# sw63_mk3_2.net
KiCad netlist of a schematic drawn in EAGLE
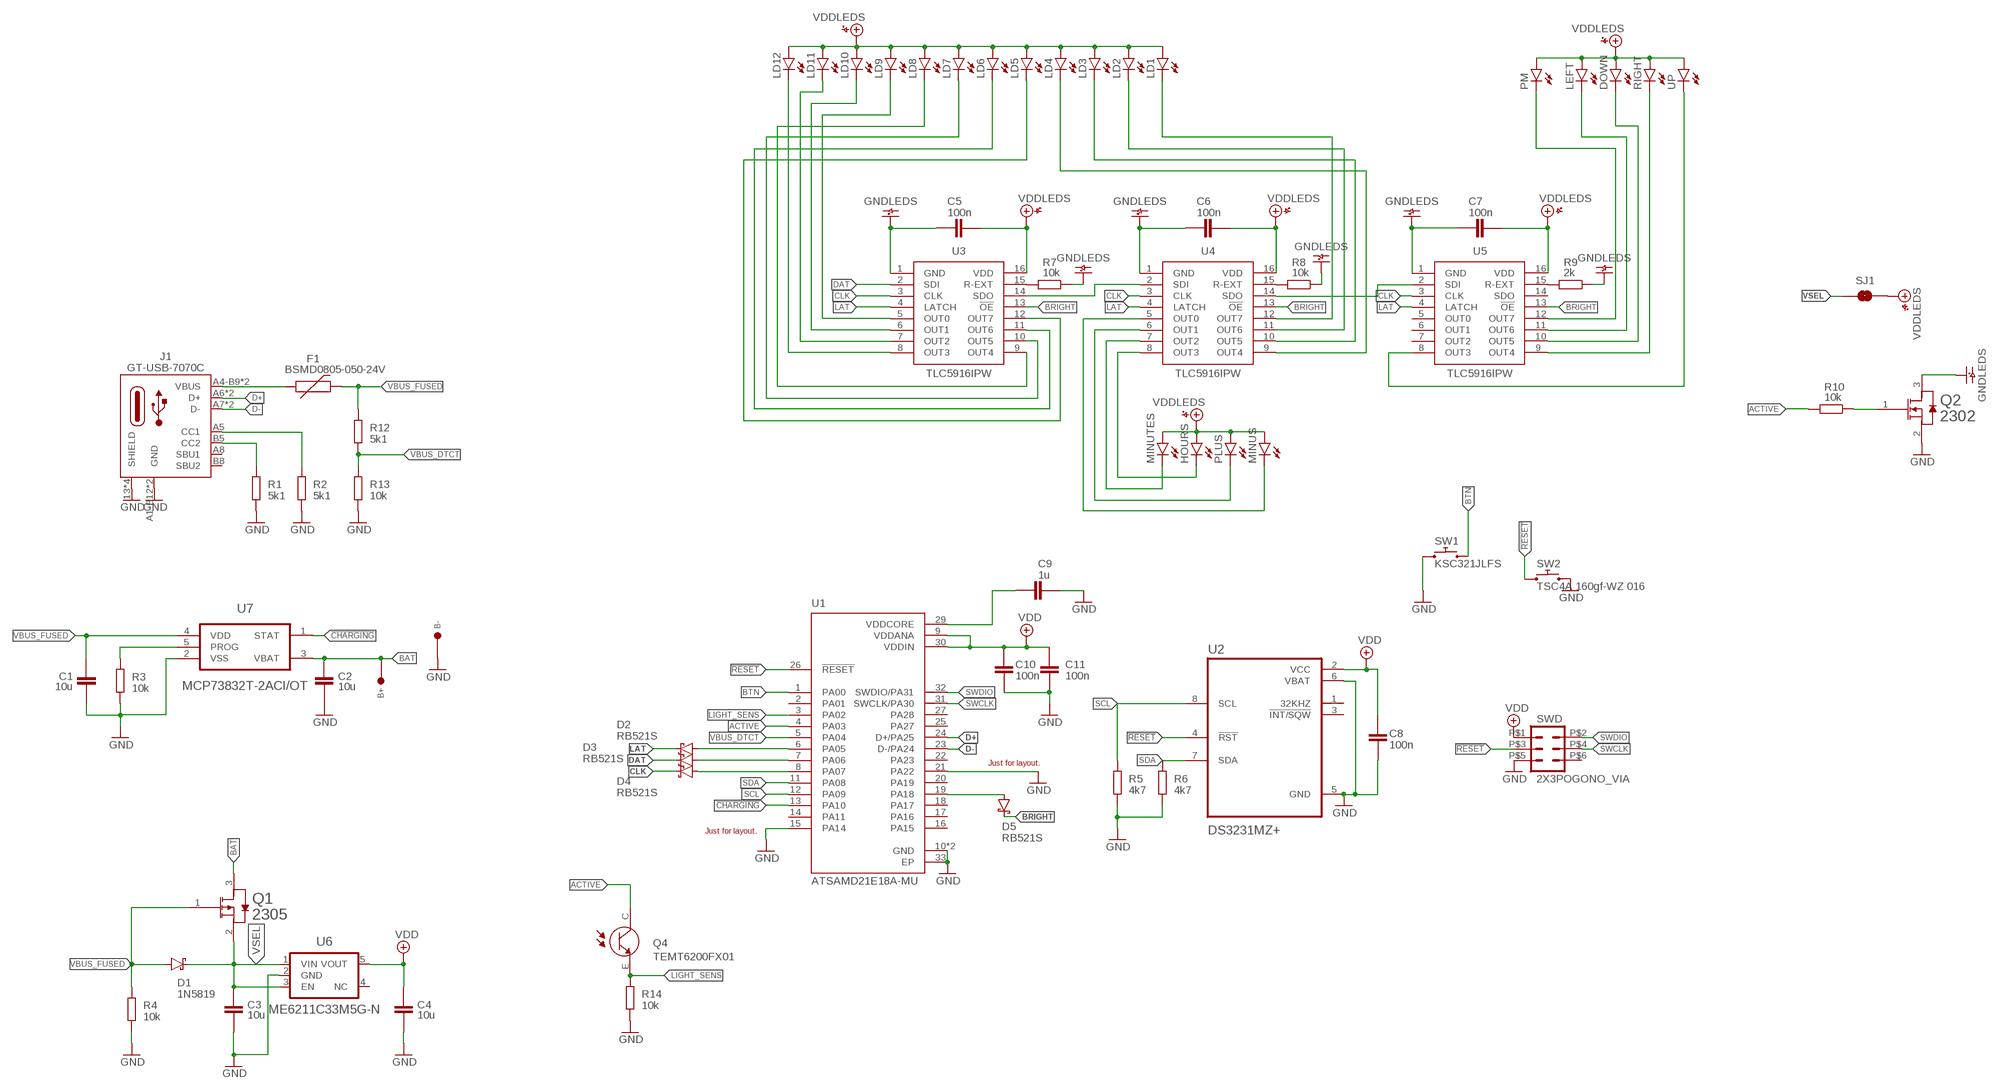
[diagram p0: schematic, sheet 1]

(export (version "E")
  (design (tool "Eeschema 10.0.6"))
  (components
    (comp (ref "B+")
      (value "TEST_PIN_LARGE")
      (footprint "eagle-import:TEST_PIN_2.0")
      (libsource (lib "eagle-import") (part "TEST_PIN_LARGE"))
    )
    (comp (ref "B-")
      (value "TEST_PIN_LARGE")
      (footprint "eagle-import:TEST_PIN_2.0")
      (libsource (lib "eagle-import") (part "TEST_PIN_LARGE"))
    )
    (comp (ref "C1")
      (value "10u")
      (footprint "eagle-import:CAPACITOR0805")
      (libsource (lib "eagle-import") (part "CAPACITOR0805"))
    )
    (comp (ref "C2")
      (value "10u")
      (footprint "eagle-import:CAPACITOR0805")
      (libsource (lib "eagle-import") (part "CAPACITOR0805"))
    )
    (comp (ref "C3")
      (value "10u")
      (footprint "eagle-import:CAPACITOR0805")
      (libsource (lib "eagle-import") (part "CAPACITOR0805"))
    )
    (comp (ref "C4")
      (value "10u")
      (footprint "eagle-import:CAPACITOR0805")
      (libsource (lib "eagle-import") (part "CAPACITOR0805"))
    )
    (comp (ref "C5")
      (value "100n")
      (footprint "eagle-import:CAPACITOR0603")
      (libsource (lib "eagle-import") (part "CAPACITOR0603"))
    )
    (comp (ref "C6")
      (value "100n")
      (footprint "eagle-import:CAPACITOR0603")
      (libsource (lib "eagle-import") (part "CAPACITOR0603"))
    )
    (comp (ref "C7")
      (value "100n")
      (footprint "eagle-import:CAPACITOR0603")
      (libsource (lib "eagle-import") (part "CAPACITOR0603"))
    )
    (comp (ref "C8")
      (value "100n")
      (footprint "eagle-import:CAPACITOR0603")
      (libsource (lib "eagle-import") (part "CAPACITOR0603"))
    )
    (comp (ref "C9")
      (value "1u")
      (footprint "eagle-import:CAPACITOR0603")
      (libsource (lib "eagle-import") (part "CAPACITOR0603"))
    )
    (comp (ref "C10")
      (value "100n")
      (footprint "eagle-import:CAPACITOR0603")
      (libsource (lib "eagle-import") (part "CAPACITOR0603"))
    )
    (comp (ref "C11")
      (value "100n")
      (footprint "eagle-import:CAPACITOR0603")
      (libsource (lib "eagle-import") (part "CAPACITOR0603"))
    )
    (comp (ref "D1")
      (value "1N5819")
      (footprint "eagle-import:SOD123")
      (libsource (lib "eagle-import") (part "SCHOTTKY_DIODE"))
    )
    (comp (ref "D2")
      (value "RB521S")
      (footprint "eagle-import:SOD523")
      (libsource (lib "eagle-import") (part "SCHOTTKY_DIODE_SOD523"))
    )
    (comp (ref "D3")
      (value "RB521S")
      (footprint "eagle-import:SOD523")
      (libsource (lib "eagle-import") (part "SCHOTTKY_DIODE_SOD523"))
    )
    (comp (ref "D4")
      (value "RB521S")
      (footprint "eagle-import:SOD523")
      (libsource (lib "eagle-import") (part "SCHOTTKY_DIODE_SOD523"))
    )
    (comp (ref "D5")
      (value "RB521S")
      (footprint "eagle-import:SOD523")
      (libsource (lib "eagle-import") (part "SCHOTTKY_DIODE_SOD523"))
    )
    (comp (ref "DOWN")
      (value "LED_RECT-3.2X2")
      (footprint "eagle-import:LED_RECT_3.2X2")
      (libsource (lib "eagle-import") (part "LED_RECT-3.2X2"))
    )
    (comp (ref "F1")
      (value "BSMD0805-050-24V")
      (footprint "eagle-import:PTC0805")
      (libsource (lib "eagle-import") (part "PTC"))
    )
    (comp (ref "HOURS")
      (value "LED_THT-5MM_B")
      (footprint "eagle-import:LED_5MM_BLUE")
      (libsource (lib "eagle-import") (part "LED_THT-5MM_B"))
    )
    (comp (ref "J1")
      (value "GT-USB-7070C")
      (footprint "eagle-import:USB-C_FULL_SMT_WS")
      (libsource (lib "eagle-import") (part "USB-C_2.0_SMT_WS"))
    )
    (comp (ref "LD1")
      (value "LED_SMT_1206")
      (footprint "eagle-import:LED_1206")
      (libsource (lib "eagle-import") (part "LED_SMT_1206"))
    )
    (comp (ref "LD2")
      (value "LED_SMT_1206")
      (footprint "eagle-import:LED_1206")
      (libsource (lib "eagle-import") (part "LED_SMT_1206"))
    )
    (comp (ref "LD3")
      (value "LED_SMT_1206")
      (footprint "eagle-import:LED_1206")
      (libsource (lib "eagle-import") (part "LED_SMT_1206"))
    )
    (comp (ref "LD4")
      (value "LED_SMT_1206")
      (footprint "eagle-import:LED_1206")
      (libsource (lib "eagle-import") (part "LED_SMT_1206"))
    )
    (comp (ref "LD5")
      (value "LED_SMT_1206")
      (footprint "eagle-import:LED_1206")
      (libsource (lib "eagle-import") (part "LED_SMT_1206"))
    )
    (comp (ref "LD6")
      (value "LED_SMT_1206")
      (footprint "eagle-import:LED_1206")
      (libsource (lib "eagle-import") (part "LED_SMT_1206"))
    )
    (comp (ref "LD7")
      (value "LED_SMT_1206")
      (footprint "eagle-import:LED_1206")
      (libsource (lib "eagle-import") (part "LED_SMT_1206"))
    )
    (comp (ref "LD8")
      (value "LED_SMT_1206")
      (footprint "eagle-import:LED_1206")
      (libsource (lib "eagle-import") (part "LED_SMT_1206"))
    )
    (comp (ref "LD9")
      (value "LED_SMT_1206")
      (footprint "eagle-import:LED_1206")
      (libsource (lib "eagle-import") (part "LED_SMT_1206"))
    )
    (comp (ref "LD10")
      (value "LED_SMT_1206")
      (footprint "eagle-import:LED_1206")
      (libsource (lib "eagle-import") (part "LED_SMT_1206"))
    )
    (comp (ref "LD11")
      (value "LED_SMT_1206")
      (footprint "eagle-import:LED_1206")
      (libsource (lib "eagle-import") (part "LED_SMT_1206"))
    )
    (comp (ref "LD12")
      (value "LED_SMT_1206")
      (footprint "eagle-import:LED_1206")
      (libsource (lib "eagle-import") (part "LED_SMT_1206"))
    )
    (comp (ref "LEFT")
      (value "LED_RECT-3.2X2")
      (footprint "eagle-import:LED_RECT_3.2X2")
      (libsource (lib "eagle-import") (part "LED_RECT-3.2X2"))
    )
    (comp (ref "MINUS")
      (value "LED_THT-5MM_R")
      (footprint "eagle-import:LED_5MM_RED")
      (libsource (lib "eagle-import") (part "LED_THT-5MM_R"))
    )
    (comp (ref "MINUTES")
      (value "LED_THT-5MM_Y")
      (footprint "eagle-import:LED_5MM_YELLOW")
      (libsource (lib "eagle-import") (part "LED_THT-5MM_Y"))
    )
    (comp (ref "PLUS")
      (value "LED_THT-5MM_G")
      (footprint "eagle-import:LED_5MM_GREEN")
      (libsource (lib "eagle-import") (part "LED_THT-5MM_G"))
    )
    (comp (ref "PM")
      (value "LED_THT-3MM_ALT")
      (footprint "eagle-import:LED_3MM_ALT")
      (libsource (lib "eagle-import") (part "LED_THT-3MM_ALT"))
    )
    (comp (ref "Q1")
      (value "2305")
      (footprint "eagle-import:SOT23")
      (libsource (lib "eagle-import") (part "LGE2305"))
    )
    (comp (ref "Q2")
      (value "2302")
      (footprint "eagle-import:SOT23")
      (libsource (lib "eagle-import") (part "N-MOSFET"))
    )
    (comp (ref "Q4")
      (value "TEMT6200FX01")
      (footprint "eagle-import:TEMT6200FX01")
      (fields (field (name "MF") "Vishay Semiconductor"))
      (libsource (lib "eagle-import") (part "TEMT6200FX01"))
    )
    (comp (ref "R1")
      (value "5k1")
      (footprint "eagle-import:RESISTOR0603")
      (libsource (lib "eagle-import") (part "RESISTOR0603"))
    )
    (comp (ref "R2")
      (value "5k1")
      (footprint "eagle-import:RESISTOR0603")
      (libsource (lib "eagle-import") (part "RESISTOR0603"))
    )
    (comp (ref "R3")
      (value "10k")
      (footprint "eagle-import:RESISTOR0603")
      (libsource (lib "eagle-import") (part "RESISTOR0603"))
    )
    (comp (ref "R4")
      (value "10k")
      (footprint "eagle-import:RESISTOR0603")
      (libsource (lib "eagle-import") (part "RESISTOR0603"))
    )
    (comp (ref "R5")
      (value "4k7")
      (footprint "eagle-import:RESISTOR0603")
      (libsource (lib "eagle-import") (part "RESISTOR0603"))
    )
    (comp (ref "R6")
      (value "4k7")
      (footprint "eagle-import:RESISTOR0603")
      (libsource (lib "eagle-import") (part "RESISTOR0603"))
    )
    (comp (ref "R7")
      (value "10k")
      (footprint "eagle-import:RESISTOR0603")
      (libsource (lib "eagle-import") (part "RESISTOR0603"))
    )
    (comp (ref "R8")
      (value "10k")
      (footprint "eagle-import:RESISTOR0603")
      (libsource (lib "eagle-import") (part "RESISTOR0603"))
    )
    (comp (ref "R9")
      (value "2k")
      (footprint "eagle-import:RESISTOR0603")
      (libsource (lib "eagle-import") (part "RESISTOR0603"))
    )
    (comp (ref "R10")
      (value "10k")
      (footprint "eagle-import:RESISTOR0603")
      (libsource (lib "eagle-import") (part "RESISTOR0603"))
    )
    (comp (ref "R12")
      (value "5k1")
      (footprint "eagle-import:RESISTOR0603")
      (libsource (lib "eagle-import") (part "RESISTOR0603"))
    )
    (comp (ref "R13")
      (value "10k")
      (footprint "eagle-import:RESISTOR0603")
      (libsource (lib "eagle-import") (part "RESISTOR0603"))
    )
    (comp (ref "R14")
      (value "10k")
      (footprint "eagle-import:RESISTOR0603")
      (libsource (lib "eagle-import") (part "RESISTOR0603"))
    )
    (comp (ref "RIGHT")
      (value "LED_RECT-3.2X2")
      (footprint "eagle-import:LED_RECT_3.2X2")
      (libsource (lib "eagle-import") (part "LED_RECT-3.2X2"))
    )
    (comp (ref "SJ1")
      (value "SMALL_NC")
      (footprint "eagle-import:SMALL_NC_NOSILK")
      (libsource (lib "eagle-import") (part "SMALL_NC"))
    )
    (comp (ref "SW1")
      (value "KSC321JLFS")
      (footprint "eagle-import:KSC3XXJ")
      (libsource (lib "eagle-import") (part "KSC3XXJ"))
    )
    (comp (ref "SW2")
      (value "TSC4A 160gf-WZ 016")
      (footprint "eagle-import:EVQ-P7J01P")
      (libsource (lib "eagle-import") (part "EVQ-P7J01P"))
    )
    (comp (ref "SWD")
      (value "2X3POGONO_VIA")
      (footprint "eagle-import:2X3_POGO_NO_VIA")
      (libsource (lib "eagle-import") (part "2X3POGONO_VIA"))
    )
    (comp (ref "U1")
      (value "ATSAMD21E18A-MU")
      (footprint "eagle-import:QFN50P500X500X100-33N")
      (fields (field (name "DIGIKEY_PART_NUMBER") "ATSAMD21E18A-MU-ND") (field (name "MF") "Microchip"))
      (libsource (lib "eagle-import") (part "ATSAMD21E18A-MU"))
    )
    (comp (ref "U2")
      (value "DS3231MZ+")
      (footprint "eagle-import:SO8")
      (fields
        (field (name "DIGI-KEY_PART_NUMBER") "DS3231MZ+-ND")
        (field (name "MF") "Maxim Integrated Products")
      )
      (libsource (lib "eagle-import") (part "DS3231MZ+"))
    )
    (comp (ref "U3")
      (value "TLC5916IPW")
      (footprint "eagle-import:TSSOP16")
      (libsource (lib "eagle-import") (part "TLC5916IPW"))
    )
    (comp (ref "U4")
      (value "TLC5916IPW")
      (footprint "eagle-import:TSSOP16")
      (libsource (lib "eagle-import") (part "TLC5916IPW"))
    )
    (comp (ref "U5")
      (value "TLC5916IPW")
      (footprint "eagle-import:TSSOP16")
      (libsource (lib "eagle-import") (part "TLC5916IPW"))
    )
    (comp (ref "U6")
      (value "ME6211C33M5G-N")
      (footprint "eagle-import:SOT23-5")
      (libsource (lib "eagle-import") (part "MIC5504YM5-TR"))
    )
    (comp (ref "U7")
      (value "MCP73832T-2ACI/OT")
      (footprint "eagle-import:SOT23-5")
      (fields (field (name "MPN") "MCP73831T-2ACI/OT"))
      (libsource (lib "eagle-import") (part "MCP73831T-2ACI"))
    )
    (comp (ref "UP")
      (value "LED_RECT-3.2X2")
      (footprint "eagle-import:LED_RECT_3.2X2")
      (libsource (lib "eagle-import") (part "LED_RECT-3.2X2"))
    )
  )
  (nets
    (net (code "1") (name "/~{CHARGING}") (class "Default")
      (node (ref "U1") (pin "13") (pinfunction "PA10_13") (pintype "bidirectional"))
      (node (ref "U7") (pin "1") (pinfunction "STAT_1") (pintype "output"))
    )
    (net (code "2") (name "/~{RESET}") (class "Default")
      (node (ref "SW2") (pin "1_1") (pinfunction "1_1_1") (pintype "passive"))
      (node (ref "SW2") (pin "1_2") (pinfunction "1_1_2") (pintype "passive"))
      (node (ref "SWD") (pin "P$3") (pinfunction "3_P$3") (pintype "passive"))
      (node (ref "U1") (pin "26") (pinfunction "~{RESET}_26") (pintype "input"))
      (node (ref "U2") (pin "4") (pinfunction "~{RST}_4") (pintype "bidirectional"))
    )
    (net (code "3") (name "ACTIVE") (class "Default")
      (node (ref "Q4") (pin "C") (pinfunction "C_C") (pintype "passive"))
      (node (ref "R10") (pin "2") (pinfunction "2_2") (pintype "passive"))
      (node (ref "U1") (pin "4") (pinfunction "PA03_4") (pintype "bidirectional"))
    )
    (net (code "4") (name "BAT") (class "Default")
      (node (ref "B+") (pin "P$1") (pinfunction "P$1_P$1") (pintype "bidirectional"))
      (node (ref "C2") (pin "1") (pinfunction "1_1") (pintype "passive"))
      (node (ref "Q1") (pin "3") (pinfunction "DRAIN_3") (pintype "passive"))
      (node (ref "U7") (pin "3") (pinfunction "VBAT_3") (pintype "output"))
    )
    (net (code "5") (name "BRIGHT") (class "Default")
      (node (ref "D5") (pin "C") (pinfunction "C_C") (pintype "passive"))
      (node (ref "U3") (pin "13") (pinfunction "~{OE}_13") (pintype "input"))
      (node (ref "U4") (pin "13") (pinfunction "~{OE}_13") (pintype "input"))
      (node (ref "U5") (pin "13") (pinfunction "~{OE}_13") (pintype "input"))
    )
    (net (code "6") (name "BTN") (class "Default")
      (node (ref "SW1") (pin "2") (pinfunction "2_2") (pintype "passive"))
      (node (ref "SW1") (pin "4") (pinfunction "2_4") (pintype "passive"))
      (node (ref "U1") (pin "1") (pinfunction "PA00_1") (pintype "bidirectional"))
    )
    (net (code "7") (name "CLK") (class "Default")
      (node (ref "D4") (pin "C") (pinfunction "C_C") (pintype "passive"))
      (node (ref "U3") (pin "3") (pinfunction "CLK_3") (pintype "input"))
      (node (ref "U4") (pin "3") (pinfunction "CLK_3") (pintype "input"))
      (node (ref "U5") (pin "3") (pinfunction "CLK_3") (pintype "input"))
    )
    (net (code "8") (name "D+") (class "Default")
      (node (ref "J1") (pin "A6") (pinfunction "D+_A6") (pintype "bidirectional"))
      (node (ref "J1") (pin "B6") (pinfunction "D+_B6") (pintype "bidirectional"))
      (node (ref "U1") (pin "24") (pinfunction "D+/PA25_24") (pintype "bidirectional"))
    )
    (net (code "9") (name "D-") (class "Default")
      (node (ref "J1") (pin "A7") (pinfunction "D-_A7") (pintype "bidirectional"))
      (node (ref "J1") (pin "B7") (pinfunction "D-_B7") (pintype "bidirectional"))
      (node (ref "U1") (pin "23") (pinfunction "D-/PA24_23") (pintype "bidirectional"))
    )
    (net (code "10") (name "DAT") (class "Default")
      (node (ref "D3") (pin "C") (pinfunction "C_C") (pintype "passive"))
      (node (ref "U3") (pin "2") (pinfunction "SDI_2") (pintype "input"))
    )
    (net (code "11") (name "GND") (class "Default")
      (node (ref "B-") (pin "P$1") (pinfunction "P$1_P$1") (pintype "bidirectional"))
      (node (ref "C1") (pin "2") (pinfunction "2_2") (pintype "passive"))
      (node (ref "C10") (pin "1") (pinfunction "1_1") (pintype "passive"))
      (node (ref "C11") (pin "1") (pinfunction "1_1") (pintype "passive"))
      (node (ref "C2") (pin "2") (pinfunction "2_2") (pintype "passive"))
      (node (ref "C3") (pin "2") (pinfunction "2_2") (pintype "passive"))
      (node (ref "C4") (pin "2") (pinfunction "2_2") (pintype "passive"))
      (node (ref "C8") (pin "2") (pinfunction "2_2") (pintype "passive"))
      (node (ref "C9") (pin "1") (pinfunction "1_1") (pintype "passive"))
      (node (ref "J1") (pin "13") (pinfunction "SHIELD_13") (pintype "bidirectional"))
      (node (ref "J1") (pin "14") (pinfunction "SHIELD_14") (pintype "bidirectional"))
      (node (ref "J1") (pin "15") (pinfunction "SHIELD_15") (pintype "bidirectional"))
      (node (ref "J1") (pin "16") (pinfunction "SHIELD_16") (pintype "bidirectional"))
      (node (ref "J1") (pin "A1-B12") (pinfunction "GND_A1-B12") (pintype "passive"))
      (node (ref "J1") (pin "B1-A12") (pinfunction "GND_B1-A12") (pintype "passive"))
      (node (ref "Q2") (pin "2") (pinfunction "SOURCE_2") (pintype "passive"))
      (node (ref "R1") (pin "1") (pinfunction "1_1") (pintype "passive"))
      (node (ref "R13") (pin "1") (pinfunction "1_1") (pintype "passive"))
      (node (ref "R14") (pin "1") (pinfunction "1_1") (pintype "passive"))
      (node (ref "R2") (pin "1") (pinfunction "1_1") (pintype "passive"))
      (node (ref "R3") (pin "1") (pinfunction "1_1") (pintype "passive"))
      (node (ref "R4") (pin "1") (pinfunction "1_1") (pintype "passive"))
      (node (ref "R5") (pin "1") (pinfunction "1_1") (pintype "passive"))
      (node (ref "R6") (pin "1") (pinfunction "1_1") (pintype "passive"))
      (node (ref "SW1") (pin "1") (pinfunction "1_1") (pintype "passive"))
      (node (ref "SW1") (pin "3") (pinfunction "1_3") (pintype "passive"))
      (node (ref "SW2") (pin "2_1") (pinfunction "2_2_1") (pintype "passive"))
      (node (ref "SW2") (pin "2_2") (pinfunction "2_2_2") (pintype "passive"))
      (node (ref "SWD") (pin "P$5") (pinfunction "5_P$5") (pintype "passive"))
      (node (ref "U1") (pin "10") (pinfunction "GND_10") (pintype "power_in"))
      (node (ref "U1") (pin "15") (pinfunction "PA14_15") (pintype "bidirectional"))
      (node (ref "U1") (pin "21") (pinfunction "PA22_21") (pintype "bidirectional"))
      (node (ref "U1") (pin "28") (pinfunction "GND_28") (pintype "power_in"))
      (node (ref "U1") (pin "33") (pinfunction "EP_33") (pintype "power_in"))
      (node (ref "U2") (pin "5") (pinfunction "GND_5") (pintype "power_in"))
      (node (ref "U2") (pin "6") (pinfunction "VBAT_6") (pintype "power_in"))
      (node (ref "U6") (pin "2") (pinfunction "GND_2") (pintype "power_in"))
      (node (ref "U7") (pin "2") (pinfunction "VSS_2") (pintype "power_in"))
    )
    (net (code "12") (name "GNDLEDS") (class "Default")
      (node (ref "C5") (pin "1") (pinfunction "1_1") (pintype "passive"))
      (node (ref "C6") (pin "1") (pinfunction "1_1") (pintype "passive"))
      (node (ref "C7") (pin "1") (pinfunction "1_1") (pintype "passive"))
      (node (ref "Q2") (pin "3") (pinfunction "DRAIN_3") (pintype "passive"))
      (node (ref "R7") (pin "1") (pinfunction "1_1") (pintype "passive"))
      (node (ref "R8") (pin "1") (pinfunction "1_1") (pintype "passive"))
      (node (ref "R9") (pin "1") (pinfunction "1_1") (pintype "passive"))
      (node (ref "U3") (pin "1") (pinfunction "GND_1") (pintype "power_in"))
      (node (ref "U4") (pin "1") (pinfunction "GND_1") (pintype "power_in"))
      (node (ref "U5") (pin "1") (pinfunction "GND_1") (pintype "power_in"))
    )
    (net (code "13") (name "LAT") (class "Default")
      (node (ref "D2") (pin "C") (pinfunction "C_C") (pintype "passive"))
      (node (ref "U3") (pin "4") (pinfunction "LATCH_4") (pintype "input"))
      (node (ref "U4") (pin "4") (pinfunction "LATCH_4") (pintype "input"))
      (node (ref "U5") (pin "4") (pinfunction "LATCH_4") (pintype "input"))
    )
    (net (code "14") (name "LIGHT_SENS") (class "Default")
      (node (ref "Q4") (pin "E") (pinfunction "E_E") (pintype "passive"))
      (node (ref "R14") (pin "2") (pinfunction "2_2") (pintype "passive"))
      (node (ref "U1") (pin "3") (pinfunction "PA02_3") (pintype "bidirectional"))
    )
    (net (code "15") (name "Net-(DOWN-C)") (class "Default")
      (node (ref "DOWN") (pin "K") (pinfunction "C_K") (pintype "passive"))
      (node (ref "U5") (pin "10") (pinfunction "OUT5_10") (pintype "output"))
    )
    (net (code "16") (name "Net-(F1-1)") (class "Default")
      (node (ref "F1") (pin "2") (pinfunction "1_2") (pintype "bidirectional"))
      (node (ref "J1") (pin "A4-B9") (pinfunction "VBUS_A4-B9") (pintype "power_in"))
      (node (ref "J1") (pin "B4-A9") (pinfunction "VBUS_B4-A9") (pintype "power_in"))
    )
    (net (code "17") (name "Net-(HOURS-C)") (class "Default")
      (node (ref "HOURS") (pin "K") (pinfunction "C_K") (pintype "passive"))
      (node (ref "U4") (pin "8") (pinfunction "OUT3_8") (pintype "output"))
    )
    (net (code "18") (name "Net-(J1-CC1)") (class "Default")
      (node (ref "J1") (pin "A5") (pinfunction "CC1_A5") (pintype "bidirectional"))
      (node (ref "R2") (pin "2") (pinfunction "2_2") (pintype "passive"))
    )
    (net (code "19") (name "Net-(J1-CC2)") (class "Default")
      (node (ref "J1") (pin "B5") (pinfunction "CC2_B5") (pintype "bidirectional"))
      (node (ref "R1") (pin "2") (pinfunction "2_2") (pintype "passive"))
    )
    (net (code "20") (name "Net-(LEFT-C)") (class "Default")
      (node (ref "LEFT") (pin "K") (pinfunction "C_K") (pintype "passive"))
      (node (ref "U5") (pin "11") (pinfunction "OUT6_11") (pintype "output"))
    )
    (net (code "21") (name "Net-(MINUS-C)") (class "Default")
      (node (ref "MINUS") (pin "K") (pinfunction "C_K") (pintype "passive"))
      (node (ref "U4") (pin "5") (pinfunction "OUT0_5") (pintype "output"))
    )
    (net (code "22") (name "Net-(MINUTES-C)") (class "Default")
      (node (ref "MINUTES") (pin "K") (pinfunction "C_K") (pintype "passive"))
      (node (ref "U4") (pin "7") (pinfunction "OUT2_7") (pintype "output"))
    )
    (net (code "23") (name "Net-(PLUS-C)") (class "Default")
      (node (ref "PLUS") (pin "K") (pinfunction "C_K") (pintype "passive"))
      (node (ref "U4") (pin "6") (pinfunction "OUT1_6") (pintype "output"))
    )
    (net (code "24") (name "Net-(PM-C)") (class "Default")
      (node (ref "PM") (pin "K") (pinfunction "C_K") (pintype "passive"))
      (node (ref "U5") (pin "12") (pinfunction "OUT7_12") (pintype "output"))
    )
    (net (code "25") (name "Net-(Q2-GATE)") (class "Default")
      (node (ref "Q2") (pin "1") (pinfunction "GATE_1") (pintype "passive"))
      (node (ref "R10") (pin "1") (pinfunction "1_1") (pintype "passive"))
    )
    (net (code "26") (name "Net-(RIGHT-C)") (class "Default")
      (node (ref "RIGHT") (pin "K") (pinfunction "C_K") (pintype "passive"))
      (node (ref "U5") (pin "9") (pinfunction "OUT4_9") (pintype "output"))
    )
    (net (code "27") (name "Net-(U1-PA05)") (class "Default")
      (node (ref "D2") (pin "A") (pinfunction "A_A") (pintype "passive"))
      (node (ref "U1") (pin "6") (pinfunction "PA05_6") (pintype "bidirectional"))
    )
    (net (code "28") (name "Net-(U1-PA06)") (class "Default")
      (node (ref "D3") (pin "A") (pinfunction "A_A") (pintype "passive"))
      (node (ref "U1") (pin "7") (pinfunction "PA06_7") (pintype "bidirectional"))
    )
    (net (code "29") (name "Net-(U1-PA07)") (class "Default")
      (node (ref "D4") (pin "A") (pinfunction "A_A") (pintype "passive"))
      (node (ref "U1") (pin "8") (pinfunction "PA07_8") (pintype "bidirectional"))
    )
    (net (code "30") (name "Net-(U1-PA18)") (class "Default")
      (node (ref "D5") (pin "A") (pinfunction "A_A") (pintype "passive"))
      (node (ref "U1") (pin "19") (pinfunction "PA18_19") (pintype "bidirectional"))
    )
    (net (code "31") (name "Net-(U1-VDDCORE)") (class "Default")
      (node (ref "C9") (pin "2") (pinfunction "2_2") (pintype "passive"))
      (node (ref "U1") (pin "29") (pinfunction "VDDCORE_29") (pintype "power_in"))
    )
    (net (code "32") (name "Net-(U3-OUT0)") (class "Default")
      (node (ref "LD9") (pin "C") (pinfunction "C_C") (pintype "passive"))
      (node (ref "U3") (pin "5") (pinfunction "OUT0_5") (pintype "output"))
    )
    (net (code "33") (name "Net-(U3-OUT1)") (class "Default")
      (node (ref "LD10") (pin "C") (pinfunction "C_C") (pintype "passive"))
      (node (ref "U3") (pin "6") (pinfunction "OUT1_6") (pintype "output"))
    )
    (net (code "34") (name "Net-(U3-OUT2)") (class "Default")
      (node (ref "LD11") (pin "C") (pinfunction "C_C") (pintype "passive"))
      (node (ref "U3") (pin "7") (pinfunction "OUT2_7") (pintype "output"))
    )
    (net (code "35") (name "Net-(U3-OUT3)") (class "Default")
      (node (ref "LD12") (pin "C") (pinfunction "C_C") (pintype "passive"))
      (node (ref "U3") (pin "8") (pinfunction "OUT3_8") (pintype "output"))
    )
    (net (code "36") (name "Net-(U3-OUT4)") (class "Default")
      (node (ref "LD8") (pin "C") (pinfunction "C_C") (pintype "passive"))
      (node (ref "U3") (pin "9") (pinfunction "OUT4_9") (pintype "output"))
    )
    (net (code "37") (name "Net-(U3-OUT5)") (class "Default")
      (node (ref "LD7") (pin "C") (pinfunction "C_C") (pintype "passive"))
      (node (ref "U3") (pin "10") (pinfunction "OUT5_10") (pintype "output"))
    )
    (net (code "38") (name "Net-(U3-OUT6)") (class "Default")
      (node (ref "LD6") (pin "C") (pinfunction "C_C") (pintype "passive"))
      (node (ref "U3") (pin "11") (pinfunction "OUT6_11") (pintype "output"))
    )
    (net (code "39") (name "Net-(U3-OUT7)") (class "Default")
      (node (ref "LD5") (pin "C") (pinfunction "C_C") (pintype "passive"))
      (node (ref "U3") (pin "12") (pinfunction "OUT7_12") (pintype "output"))
    )
    (net (code "40") (name "Net-(U3-R-EXT)") (class "Default")
      (node (ref "R7") (pin "2") (pinfunction "2_2") (pintype "passive"))
      (node (ref "U3") (pin "15") (pinfunction "R-EXT_15") (pintype "input"))
    )
    (net (code "41") (name "Net-(U3-SDO)") (class "Default")
      (node (ref "U3") (pin "14") (pinfunction "SDO_14") (pintype "output"))
      (node (ref "U4") (pin "2") (pinfunction "SDI_2") (pintype "input"))
    )
    (net (code "42") (name "Net-(U4-OUT4)") (class "Default")
      (node (ref "LD4") (pin "C") (pinfunction "C_C") (pintype "passive"))
      (node (ref "U4") (pin "9") (pinfunction "OUT4_9") (pintype "output"))
    )
    (net (code "43") (name "Net-(U4-OUT5)") (class "Default")
      (node (ref "LD3") (pin "C") (pinfunction "C_C") (pintype "passive"))
      (node (ref "U4") (pin "10") (pinfunction "OUT5_10") (pintype "output"))
    )
    (net (code "44") (name "Net-(U4-OUT6)") (class "Default")
      (node (ref "LD2") (pin "C") (pinfunction "C_C") (pintype "passive"))
      (node (ref "U4") (pin "11") (pinfunction "OUT6_11") (pintype "output"))
    )
    (net (code "45") (name "Net-(U4-OUT7)") (class "Default")
      (node (ref "LD1") (pin "C") (pinfunction "C_C") (pintype "passive"))
      (node (ref "U4") (pin "12") (pinfunction "OUT7_12") (pintype "output"))
    )
    (net (code "46") (name "Net-(U4-R-EXT)") (class "Default")
      (node (ref "R8") (pin "2") (pinfunction "2_2") (pintype "passive"))
      (node (ref "U4") (pin "15") (pinfunction "R-EXT_15") (pintype "input"))
    )
    (net (code "47") (name "Net-(U4-SDO)") (class "Default")
      (node (ref "U4") (pin "14") (pinfunction "SDO_14") (pintype "output"))
      (node (ref "U5") (pin "2") (pinfunction "SDI_2") (pintype "input"))
    )
    (net (code "48") (name "Net-(U5-OUT3)") (class "Default")
      (node (ref "U5") (pin "8") (pinfunction "OUT3_8") (pintype "output"))
      (node (ref "UP") (pin "K") (pinfunction "C_K") (pintype "passive"))
    )
    (net (code "49") (name "Net-(U5-R-EXT)") (class "Default")
      (node (ref "R9") (pin "2") (pinfunction "2_2") (pintype "passive"))
      (node (ref "U5") (pin "15") (pinfunction "R-EXT_15") (pintype "input"))
    )
    (net (code "50") (name "Net-(U7-PROG)") (class "Default")
      (node (ref "R3") (pin "2") (pinfunction "2_2") (pintype "passive"))
      (node (ref "U7") (pin "5") (pinfunction "PROG_5") (pintype "input"))
    )
    (net (code "51") (name "SCL") (class "Default")
      (node (ref "R5") (pin "2") (pinfunction "2_2") (pintype "passive"))
      (node (ref "U1") (pin "12") (pinfunction "PA09_12") (pintype "bidirectional"))
      (node (ref "U2") (pin "8") (pinfunction "SCL_8") (pintype "input"))
    )
    (net (code "52") (name "SDA") (class "Default")
      (node (ref "R6") (pin "2") (pinfunction "2_2") (pintype "passive"))
      (node (ref "U1") (pin "11") (pinfunction "PA08_11") (pintype "bidirectional"))
      (node (ref "U2") (pin "7") (pinfunction "SDA_7") (pintype "bidirectional"))
    )
    (net (code "53") (name "SWCLK") (class "Default")
      (node (ref "SWD") (pin "P$4") (pinfunction "4_P$4") (pintype "passive"))
      (node (ref "U1") (pin "31") (pinfunction "SWCLK/PA30_31") (pintype "bidirectional"))
    )
    (net (code "54") (name "SWDIO") (class "Default")
      (node (ref "SWD") (pin "P$2") (pinfunction "2_P$2") (pintype "passive"))
      (node (ref "U1") (pin "32") (pinfunction "SWDIO/PA31_32") (pintype "bidirectional"))
    )
    (net (code "55") (name "VBUS_DTCT") (class "Default")
      (node (ref "R12") (pin "1") (pinfunction "1_1") (pintype "passive"))
      (node (ref "R13") (pin "2") (pinfunction "2_2") (pintype "passive"))
      (node (ref "U1") (pin "5") (pinfunction "PA04_5") (pintype "bidirectional"))
    )
    (net (code "56") (name "VBUS_FUSED") (class "Default")
      (node (ref "C1") (pin "1") (pinfunction "1_1") (pintype "passive"))
      (node (ref "D1") (pin "A") (pinfunction "A_A") (pintype "passive"))
      (node (ref "F1") (pin "3") (pinfunction "2_3") (pintype "bidirectional"))
      (node (ref "Q1") (pin "1") (pinfunction "GATE_1") (pintype "passive"))
      (node (ref "R12") (pin "2") (pinfunction "2_2") (pintype "passive"))
      (node (ref "R4") (pin "2") (pinfunction "2_2") (pintype "passive"))
      (node (ref "U7") (pin "4") (pinfunction "VDD_4") (pintype "power_in"))
    )
    (net (code "57") (name "VDD") (class "Default")
      (node (ref "C10") (pin "2") (pinfunction "2_2") (pintype "passive"))
      (node (ref "C11") (pin "2") (pinfunction "2_2") (pintype "passive"))
      (node (ref "C4") (pin "1") (pinfunction "1_1") (pintype "passive"))
      (node (ref "C8") (pin "1") (pinfunction "1_1") (pintype "passive"))
      (node (ref "SWD") (pin "P$1") (pinfunction "1_P$1") (pintype "passive"))
      (node (ref "U1") (pin "30") (pinfunction "VDDIN_30") (pintype "power_in"))
      (node (ref "U1") (pin "9") (pinfunction "VDDANA_9") (pintype "power_in"))
      (node (ref "U2") (pin "2") (pinfunction "VCC_2") (pintype "power_in"))
      (node (ref "U6") (pin "5") (pinfunction "VOUT_5") (pintype "input"))
    )
    (net (code "58") (name "VDDLEDS") (class "Default")
      (node (ref "C5") (pin "2") (pinfunction "2_2") (pintype "passive"))
      (node (ref "C6") (pin "2") (pinfunction "2_2") (pintype "passive"))
      (node (ref "C7") (pin "2") (pinfunction "2_2") (pintype "passive"))
      (node (ref "DOWN") (pin "A") (pinfunction "A_A") (pintype "passive"))
      (node (ref "HOURS") (pin "A") (pinfunction "A_A") (pintype "passive"))
      (node (ref "LD1") (pin "A") (pinfunction "A_A") (pintype "passive"))
      (node (ref "LD10") (pin "A") (pinfunction "A_A") (pintype "passive"))
      (node (ref "LD11") (pin "A") (pinfunction "A_A") (pintype "passive"))
      (node (ref "LD12") (pin "A") (pinfunction "A_A") (pintype "passive"))
      (node (ref "LD2") (pin "A") (pinfunction "A_A") (pintype "passive"))
      (node (ref "LD3") (pin "A") (pinfunction "A_A") (pintype "passive"))
      (node (ref "LD4") (pin "A") (pinfunction "A_A") (pintype "passive"))
      (node (ref "LD5") (pin "A") (pinfunction "A_A") (pintype "passive"))
      (node (ref "LD6") (pin "A") (pinfunction "A_A") (pintype "passive"))
      (node (ref "LD7") (pin "A") (pinfunction "A_A") (pintype "passive"))
      (node (ref "LD8") (pin "A") (pinfunction "A_A") (pintype "passive"))
      (node (ref "LD9") (pin "A") (pinfunction "A_A") (pintype "passive"))
      (node (ref "LEFT") (pin "A") (pinfunction "A_A") (pintype "passive"))
      (node (ref "MINUS") (pin "A") (pinfunction "A_A") (pintype "passive"))
      (node (ref "MINUTES") (pin "A") (pinfunction "A_A") (pintype "passive"))
      (node (ref "PLUS") (pin "A") (pinfunction "A_A") (pintype "passive"))
      (node (ref "PM") (pin "A") (pinfunction "A_A") (pintype "passive"))
      (node (ref "RIGHT") (pin "A") (pinfunction "A_A") (pintype "passive"))
      (node (ref "SJ1") (pin "2") (pinfunction "2_2") (pintype "passive"))
      (node (ref "U3") (pin "16") (pinfunction "VDD_16") (pintype "power_in"))
      (node (ref "U4") (pin "16") (pinfunction "VDD_16") (pintype "power_in"))
      (node (ref "U5") (pin "16") (pinfunction "VDD_16") (pintype "power_in"))
      (node (ref "UP") (pin "A") (pinfunction "A_A") (pintype "passive"))
    )
    (net (code "59") (name "VSEL") (class "Default")
      (node (ref "C3") (pin "1") (pinfunction "1_1") (pintype "passive"))
      (node (ref "D1") (pin "C") (pinfunction "C_C") (pintype "passive"))
      (node (ref "Q1") (pin "2") (pinfunction "SOURCE_2") (pintype "passive"))
      (node (ref "SJ1") (pin "1") (pinfunction "1_1") (pintype "passive"))
      (node (ref "U6") (pin "1") (pinfunction "VIN_1") (pintype "input"))
      (node (ref "U6") (pin "3") (pinfunction "EN_3") (pintype "input"))
    )
    (net (code "60") (name "unconnected-(J1-SBU1-PadA8)") (class "Default")
      (node (ref "J1") (pin "A8") (pinfunction "SBU1_A8") (pintype "bidirectional"))
    )
    (net (code "61") (name "unconnected-(J1-SBU2-PadB8)") (class "Default")
      (node (ref "J1") (pin "B8") (pinfunction "SBU2_B8") (pintype "bidirectional"))
    )
    (net (code "62") (name "unconnected-(SWD-6-PadP$6)") (class "Default")
      (node (ref "SWD") (pin "P$6") (pinfunction "6_P$6") (pintype "passive"))
    )
    (net (code "63") (name "unconnected-(U1-PA01-Pad2)") (class "Default")
      (node (ref "U1") (pin "2") (pinfunction "PA01_2") (pintype "bidirectional"))
    )
    (net (code "64") (name "unconnected-(U1-PA11-Pad14)") (class "Default")
      (node (ref "U1") (pin "14") (pinfunction "PA11_14") (pintype "bidirectional"))
    )
    (net (code "65") (name "unconnected-(U1-PA15-Pad16)") (class "Default")
      (node (ref "U1") (pin "16") (pinfunction "PA15_16") (pintype "bidirectional"))
    )
    (net (code "66") (name "unconnected-(U1-PA16-Pad17)") (class "Default")
      (node (ref "U1") (pin "17") (pinfunction "PA16_17") (pintype "bidirectional"))
    )
    (net (code "67") (name "unconnected-(U1-PA17-Pad18)") (class "Default")
      (node (ref "U1") (pin "18") (pinfunction "PA17_18") (pintype "bidirectional"))
    )
    (net (code "68") (name "unconnected-(U1-PA19-Pad20)") (class "Default")
      (node (ref "U1") (pin "20") (pinfunction "PA19_20") (pintype "bidirectional"))
    )
    (net (code "69") (name "unconnected-(U1-PA23-Pad22)") (class "Default")
      (node (ref "U1") (pin "22") (pinfunction "PA23_22") (pintype "bidirectional"))
    )
    (net (code "70") (name "unconnected-(U1-PA27-Pad25)") (class "Default")
      (node (ref "U1") (pin "25") (pinfunction "PA27_25") (pintype "bidirectional"))
    )
    (net (code "71") (name "unconnected-(U1-PA28-Pad27)") (class "Default")
      (node (ref "U1") (pin "27") (pinfunction "PA28_27") (pintype "bidirectional"))
    )
    (net (code "72") (name "unconnected-(U2-32KHZ-Pad1)") (class "Default")
      (node (ref "U2") (pin "1") (pinfunction "32KHZ_1") (pintype "output"))
    )
    (net (code "73") (name "unconnected-(U2-~{INT{slash}SQW}-Pad3)") (class "Default")
      (node (ref "U2") (pin "3") (pinfunction "~{INT/SQW}_3") (pintype "output"))
    )
    (net (code "74") (name "unconnected-(U5-OUT0-Pad5)") (class "Default")
      (node (ref "U5") (pin "5") (pinfunction "OUT0_5") (pintype "output"))
    )
    (net (code "75") (name "unconnected-(U5-OUT1-Pad6)") (class "Default")
      (node (ref "U5") (pin "6") (pinfunction "OUT1_6") (pintype "output"))
    )
    (net (code "76") (name "unconnected-(U5-OUT2-Pad7)") (class "Default")
      (node (ref "U5") (pin "7") (pinfunction "OUT2_7") (pintype "output"))
    )
    (net (code "77") (name "unconnected-(U5-SDO-Pad14)") (class "Default")
      (node (ref "U5") (pin "14") (pinfunction "SDO_14") (pintype "output"))
    )
    (net (code "78") (name "unconnected-(U6-NC-Pad4)") (class "Default")
      (node (ref "U6") (pin "4") (pinfunction "NC_4") (pintype "no_connect"))
    )
  )
)
